# 1_1_3_Interface_board_SWD_FLASH_IO.net
KiCad netlist of a schematic drawn in Altium Designer
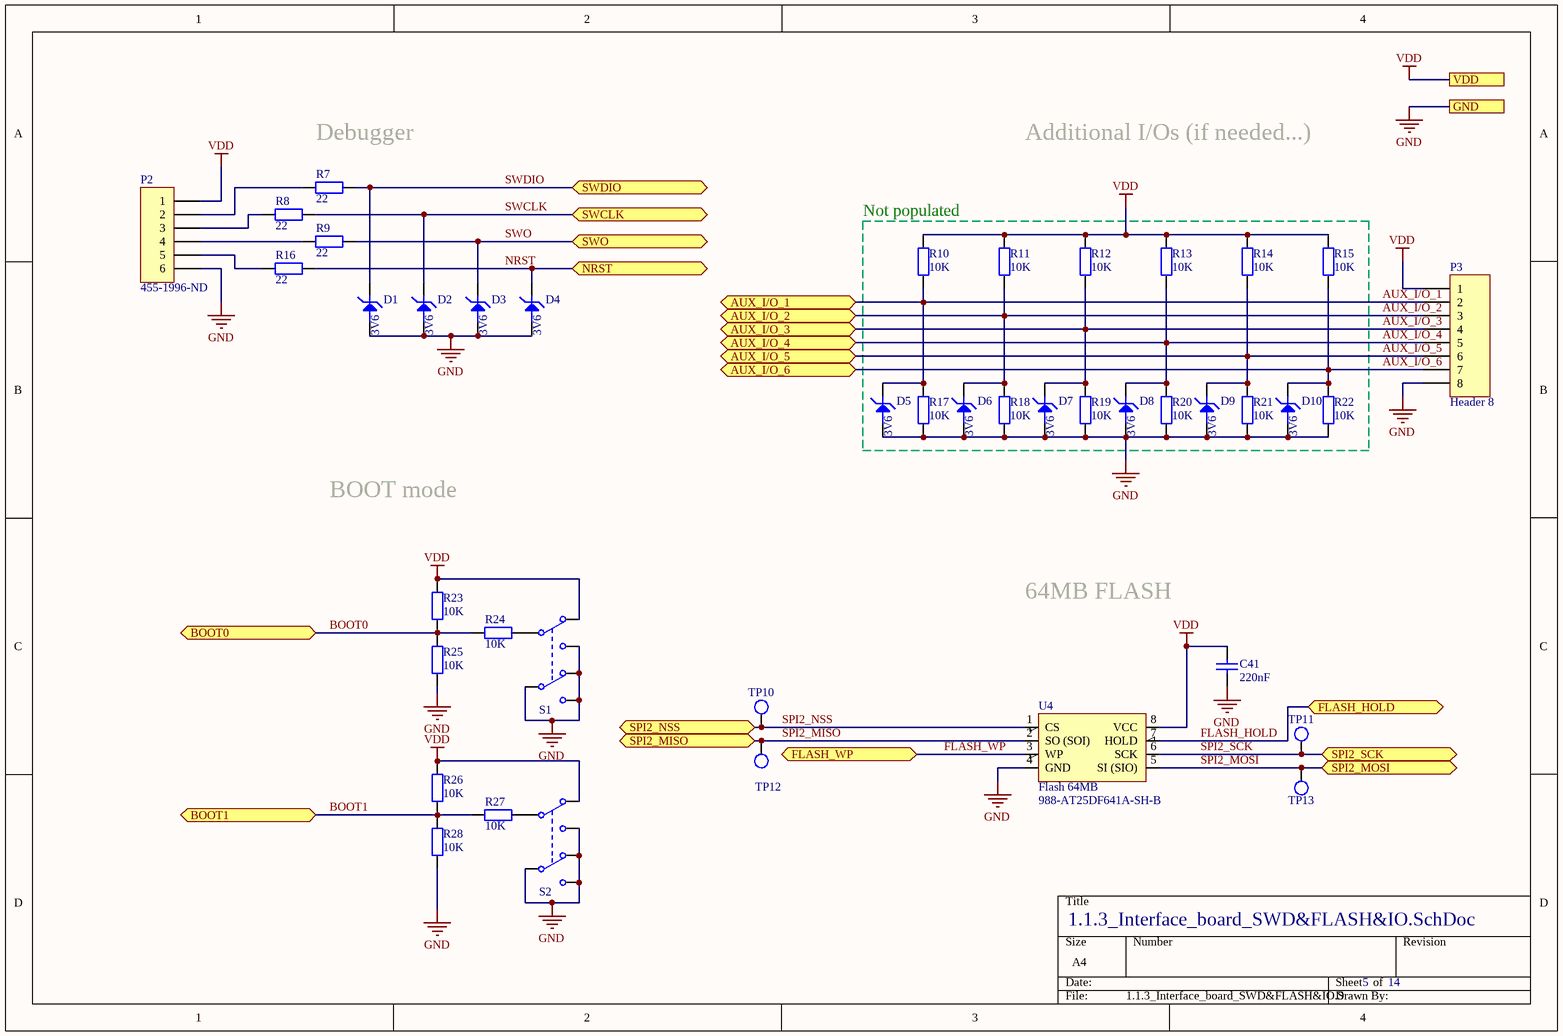
[diagram p0: 1.1.3_Interface_board_SWD&FLASH&IO.SchDoc]

(export (version "E")
  (design (tool "Eeschema 10.0.6"))
  (components
    (comp (ref "C41")
      (value "220nF")
      (footprint "CAP0603R")
      (description "Capacitor")
      (libsource (lib "Rocket_library") (part "C_220nF"))
    )
    (comp (ref "D1")
      (value "3V6")
      (footprint "SOT23")
      (description "Zener Diodes 3.6V 225mW")
      (libsource (lib "Rocket_library") (part "DZ_3V6_MMBZ522"))
    )
    (comp (ref "D2")
      (value "3V6")
      (footprint "SOT23")
      (description "Zener Diodes 3.6V 225mW")
      (libsource (lib "Rocket_library") (part "DZ_3V6_MMBZ522"))
    )
    (comp (ref "D3")
      (value "3V6")
      (footprint "SOT23")
      (description "Zener Diodes 3.6V 225mW")
      (libsource (lib "Rocket_library") (part "DZ_3V6_MMBZ522"))
    )
    (comp (ref "D4")
      (value "3V6")
      (footprint "SOT23")
      (description "Zener Diodes 3.6V 225mW")
      (libsource (lib "Rocket_library") (part "DZ_3V6_MMBZ522"))
    )
    (comp (ref "D5")
      (value "3V6")
      (footprint "SOT23")
      (description "Zener Diodes 3.6V 225mW")
      (libsource (lib "Rocket_library") (part "DZ_3V6_MMBZ522"))
    )
    (comp (ref "D6")
      (value "3V6")
      (footprint "SOT23")
      (description "Zener Diodes 3.6V 225mW")
      (libsource (lib "Rocket_library") (part "DZ_3V6_MMBZ522"))
    )
    (comp (ref "D7")
      (value "3V6")
      (footprint "SOT23")
      (description "Zener Diodes 3.6V 225mW")
      (libsource (lib "Rocket_library") (part "DZ_3V6_MMBZ522"))
    )
    (comp (ref "D8")
      (value "3V6")
      (footprint "SOT23")
      (description "Zener Diodes 3.6V 225mW")
      (libsource (lib "Rocket_library") (part "DZ_3V6_MMBZ522"))
    )
    (comp (ref "D9")
      (value "3V6")
      (footprint "SOT23")
      (description "Zener Diodes 3.6V 225mW")
      (libsource (lib "Rocket_library") (part "DZ_3V6_MMBZ522"))
    )
    (comp (ref "D10")
      (value "3V6")
      (footprint "SOT23")
      (description "Zener Diodes 3.6V 225mW")
      (libsource (lib "Rocket_library") (part "DZ_3V6_MMBZ522"))
    )
    (comp (ref "P2")
      (value "Header 6p JST XA 3A")
      (footprint "CON_JST_XA_ B06B-XASK")
      (fields (field (name "SUPPLIER PART NUMBER 1") "455-1996-ND"))
      (libsource (lib "Rocket_library") (part "Header 6p JST XA 3A"))
    )
    (comp (ref "P3")
      (value "Header 8")
      (footprint "HDR1X8")
      (description "Header, 8-Pin")
      (fields (field (name "PUBLISHER") "Altium Limited"))
      (libsource (lib "Miscellaneous Connectors") (part "Header 8"))
    )
    (comp (ref "R7")
      (value "22")
      (footprint "0603")
      (description "0.25W 22Ohm")
      (libsource (lib "Rocket_library") (part "R_0603_025W_22Ohm"))
    )
    (comp (ref "R8")
      (value "22")
      (footprint "0603")
      (description "0.25W 22Ohm")
      (libsource (lib "Rocket_library") (part "R_0603_025W_22Ohm"))
    )
    (comp (ref "R9")
      (value "22")
      (footprint "0603")
      (description "0.25W 22Ohm")
      (libsource (lib "Rocket_library") (part "R_0603_025W_22Ohm"))
    )
    (comp (ref "R10")
      (value "10K")
      (footprint "0603")
      (description "0.1W 10K")
      (libsource (lib "Rocket_library") (part "R_0603_01W_10K"))
    )
    (comp (ref "R11")
      (value "10K")
      (footprint "0603")
      (description "0.1W 10K")
      (libsource (lib "Rocket_library") (part "R_0603_01W_10K"))
    )
    (comp (ref "R12")
      (value "10K")
      (footprint "0603")
      (description "0.1W 10K")
      (libsource (lib "Rocket_library") (part "R_0603_01W_10K"))
    )
    (comp (ref "R13")
      (value "10K")
      (footprint "0603")
      (description "0.1W 10K")
      (libsource (lib "Rocket_library") (part "R_0603_01W_10K"))
    )
    (comp (ref "R14")
      (value "10K")
      (footprint "0603")
      (description "0.1W 10K")
      (libsource (lib "Rocket_library") (part "R_0603_01W_10K"))
    )
    (comp (ref "R15")
      (value "10K")
      (footprint "0603")
      (description "0.1W 10K")
      (libsource (lib "Rocket_library") (part "R_0603_01W_10K"))
    )
    (comp (ref "R16")
      (value "22")
      (footprint "0603")
      (description "0.25W 22Ohm")
      (libsource (lib "Rocket_library") (part "R_0603_025W_22Ohm"))
    )
    (comp (ref "R17")
      (value "10K")
      (footprint "0603")
      (description "0.1W 10K")
      (libsource (lib "Rocket_library") (part "R_0603_01W_10K"))
    )
    (comp (ref "R18")
      (value "10K")
      (footprint "0603")
      (description "0.1W 10K")
      (libsource (lib "Rocket_library") (part "R_0603_01W_10K"))
    )
    (comp (ref "R19")
      (value "10K")
      (footprint "0603")
      (description "0.1W 10K")
      (libsource (lib "Rocket_library") (part "R_0603_01W_10K"))
    )
    (comp (ref "R20")
      (value "10K")
      (footprint "0603")
      (description "0.1W 10K")
      (libsource (lib "Rocket_library") (part "R_0603_01W_10K"))
    )
    (comp (ref "R21")
      (value "10K")
      (footprint "0603")
      (description "0.1W 10K")
      (libsource (lib "Rocket_library") (part "R_0603_01W_10K"))
    )
    (comp (ref "R22")
      (value "10K")
      (footprint "0603")
      (description "0.1W 10K")
      (libsource (lib "Rocket_library") (part "R_0603_01W_10K"))
    )
    (comp (ref "R23")
      (value "10K")
      (footprint "0603")
      (description "0.1W 10K")
      (libsource (lib "Rocket_library") (part "R_0603_01W_10K"))
    )
    (comp (ref "R24")
      (value "10K")
      (footprint "0603")
      (description "0.1W 10K")
      (libsource (lib "") (part "R_0603_01W_10K_1"))
    )
    (comp (ref "R25")
      (value "10K")
      (footprint "0603")
      (description "0.1W 10K")
      (libsource (lib "Rocket_library") (part "R_0603_01W_10K"))
    )
    (comp (ref "R26")
      (value "10K")
      (footprint "0603")
      (description "0.1W 10K")
      (libsource (lib "Rocket_library") (part "R_0603_01W_10K"))
    )
    (comp (ref "R27")
      (value "10K")
      (footprint "0603")
      (description "0.1W 10K")
      (libsource (lib "") (part "R_0603_01W_10K_1"))
    )
    (comp (ref "R28")
      (value "10K")
      (footprint "0603")
      (description "0.1W 10K")
      (libsource (lib "Rocket_library") (part "R_0603_01W_10K"))
    )
    (comp (ref "S1")
      (value "SW DPDT")
      (footprint "SMD Slide Switches ON-ON")
      (description "Switch")
      (libsource (lib "Rocket_library") (part "SW DPDT"))
    )
    (comp (ref "S2")
      (value "SW DPDT")
      (footprint "SMD Slide Switches ON-ON")
      (description "Switch")
      (libsource (lib "Rocket_library") (part "SW DPDT"))
    )
    (comp (ref "TP10")
      (value "Test point")
      (footprint "TP")
      (libsource (lib "Rocket_library") (part "Test point"))
    )
    (comp (ref "TP11")
      (value "Test point")
      (footprint "TP")
      (libsource (lib "Rocket_library") (part "Test point"))
    )
    (comp (ref "TP12")
      (value "Test point")
      (footprint "TP")
      (libsource (lib "Rocket_library") (part "Test point"))
    )
    (comp (ref "TP13")
      (value "Test point")
      (footprint "TP")
      (libsource (lib "Rocket_library") (part "Test point"))
    )
    (comp (ref "U4")
      (value "Flash 64MB")
      (footprint "SOIC-8")
      (fields (field (name "SUPPLIER PART NUMBER 1") "988-AT25DF641A-SH-B"))
      (libsource (lib "Rocket_library") (part "Flash 64MB SPI"))
    )
  )
  (nets
    (net (code "1") (name "/AUX_I{slash}O_1") (class "Default")
      (node (ref "D5") (pin "3") (pintype "passive"))
      (node (ref "P3") (pin "2") (pinfunction "2_2") (pintype "passive"))
      (node (ref "R10") (pin "1") (pinfunction "1_1") (pintype "passive"))
      (node (ref "R17") (pin "2") (pinfunction "2_2") (pintype "passive"))
    )
    (net (code "2") (name "/AUX_I{slash}O_2") (class "Default")
      (node (ref "D6") (pin "3") (pintype "passive"))
      (node (ref "P3") (pin "3") (pinfunction "3_3") (pintype "passive"))
      (node (ref "R11") (pin "1") (pinfunction "1_1") (pintype "passive"))
      (node (ref "R18") (pin "2") (pinfunction "2_2") (pintype "passive"))
    )
    (net (code "3") (name "/AUX_I{slash}O_3") (class "Default")
      (node (ref "D7") (pin "3") (pintype "passive"))
      (node (ref "P3") (pin "4") (pinfunction "4_4") (pintype "passive"))
      (node (ref "R12") (pin "1") (pinfunction "1_1") (pintype "passive"))
      (node (ref "R19") (pin "2") (pinfunction "2_2") (pintype "passive"))
    )
    (net (code "4") (name "/AUX_I{slash}O_4") (class "Default")
      (node (ref "D8") (pin "3") (pintype "passive"))
      (node (ref "P3") (pin "5") (pinfunction "5_5") (pintype "passive"))
      (node (ref "R13") (pin "1") (pinfunction "1_1") (pintype "passive"))
      (node (ref "R20") (pin "2") (pinfunction "2_2") (pintype "passive"))
    )
    (net (code "5") (name "/AUX_I{slash}O_5") (class "Default")
      (node (ref "D9") (pin "3") (pintype "passive"))
      (node (ref "P3") (pin "6") (pinfunction "6_6") (pintype "passive"))
      (node (ref "R14") (pin "1") (pinfunction "1_1") (pintype "passive"))
      (node (ref "R21") (pin "2") (pinfunction "2_2") (pintype "passive"))
    )
    (net (code "6") (name "/AUX_I{slash}O_6") (class "Default")
      (node (ref "D10") (pin "3") (pintype "passive"))
      (node (ref "P3") (pin "7") (pinfunction "7_7") (pintype "passive"))
      (node (ref "R15") (pin "1") (pinfunction "1_1") (pintype "passive"))
      (node (ref "R22") (pin "2") (pinfunction "2_2") (pintype "passive"))
    )
    (net (code "7") (name "/BOOT0") (class "Default")
      (node (ref "R23") (pin "1") (pinfunction "1_1") (pintype "passive"))
      (node (ref "R24") (pin "2") (pinfunction "2_2") (pintype "passive"))
      (node (ref "R25") (pin "2") (pinfunction "2_2") (pintype "passive"))
    )
    (net (code "8") (name "/BOOT1") (class "Default")
      (node (ref "R26") (pin "1") (pinfunction "1_1") (pintype "passive"))
      (node (ref "R27") (pin "2") (pinfunction "2_2") (pintype "passive"))
      (node (ref "R28") (pin "2") (pinfunction "2_2") (pintype "passive"))
    )
    (net (code "9") (name "/FLASH_HOLD") (class "Default")
      (node (ref "U4") (pin "7") (pinfunction "HOLD_7") (pintype "passive"))
    )
    (net (code "10") (name "/FLASH_WP") (class "Default")
      (node (ref "U4") (pin "3") (pinfunction "WP_3") (pintype "passive"))
    )
    (net (code "11") (name "/NRST") (class "Default")
      (node (ref "D4") (pin "3") (pintype "passive"))
      (node (ref "R16") (pin "2") (pinfunction "2_2") (pintype "passive"))
    )
    (net (code "12") (name "/SPI2_MISO") (class "Default")
      (node (ref "TP12") (pin "1") (pinfunction "1_1") (pintype "passive"))
      (node (ref "U4") (pin "2") (pinfunction "SO_(SOI)_2") (pintype "passive"))
    )
    (net (code "13") (name "/SPI2_MOSI") (class "Default")
      (node (ref "TP13") (pin "1") (pinfunction "1_1") (pintype "passive"))
      (node (ref "U4") (pin "5") (pinfunction "SI_(SIO)_5") (pintype "passive"))
    )
    (net (code "14") (name "/SPI2_NSS") (class "Default")
      (node (ref "TP10") (pin "1") (pinfunction "1_1") (pintype "passive"))
      (node (ref "U4") (pin "1") (pinfunction "CS_1") (pintype "passive"))
    )
    (net (code "15") (name "/SPI2_SCK") (class "Default")
      (node (ref "TP11") (pin "1") (pinfunction "1_1") (pintype "passive"))
      (node (ref "U4") (pin "6") (pinfunction "SCK_6") (pintype "passive"))
    )
    (net (code "16") (name "/SWCLK") (class "Default")
      (node (ref "D2") (pin "3") (pintype "passive"))
      (node (ref "R8") (pin "2") (pinfunction "2_2") (pintype "passive"))
    )
    (net (code "17") (name "/SWDIO") (class "Default")
      (node (ref "D1") (pin "3") (pintype "passive"))
      (node (ref "R7") (pin "2") (pinfunction "2_2") (pintype "passive"))
    )
    (net (code "18") (name "/SWO") (class "Default")
      (node (ref "D3") (pin "3") (pintype "passive"))
      (node (ref "R9") (pin "2") (pinfunction "2_2") (pintype "passive"))
    )
    (net (code "19") (name "GND") (class "Default")
      (node (ref "C41") (pin "1") (pinfunction "1_1") (pintype "passive"))
      (node (ref "D1") (pin "1") (pintype "passive"))
      (node (ref "D10") (pin "1") (pintype "passive"))
      (node (ref "D2") (pin "1") (pintype "passive"))
      (node (ref "D3") (pin "1") (pintype "passive"))
      (node (ref "D4") (pin "1") (pintype "passive"))
      (node (ref "D5") (pin "1") (pintype "passive"))
      (node (ref "D6") (pin "1") (pintype "passive"))
      (node (ref "D7") (pin "1") (pintype "passive"))
      (node (ref "D8") (pin "1") (pintype "passive"))
      (node (ref "D9") (pin "1") (pintype "passive"))
      (node (ref "P2") (pin "6") (pinfunction "6_6") (pintype "passive"))
      (node (ref "P3") (pin "8") (pinfunction "8_8") (pintype "passive"))
      (node (ref "R17") (pin "1") (pinfunction "1_1") (pintype "passive"))
      (node (ref "R18") (pin "1") (pinfunction "1_1") (pintype "passive"))
      (node (ref "R19") (pin "1") (pinfunction "1_1") (pintype "passive"))
      (node (ref "R20") (pin "1") (pinfunction "1_1") (pintype "passive"))
      (node (ref "R21") (pin "1") (pinfunction "1_1") (pintype "passive"))
      (node (ref "R22") (pin "1") (pinfunction "1_1") (pintype "passive"))
      (node (ref "R25") (pin "1") (pinfunction "1_1") (pintype "passive"))
      (node (ref "R28") (pin "1") (pinfunction "1_1") (pintype "passive"))
      (node (ref "S1") (pin "1") (pinfunction "NO1_1") (pintype "passive"))
      (node (ref "S1") (pin "4") (pinfunction "NO2_4") (pintype "passive"))
      (node (ref "S1") (pin "5") (pinfunction "COMMON2_5") (pintype "passive"))
      (node (ref "S1") (pin "6") (pinfunction "NC2_6") (pintype "passive"))
      (node (ref "S2") (pin "1") (pinfunction "NO1_1") (pintype "passive"))
      (node (ref "S2") (pin "4") (pinfunction "NO2_4") (pintype "passive"))
      (node (ref "S2") (pin "5") (pinfunction "COMMON2_5") (pintype "passive"))
      (node (ref "S2") (pin "6") (pinfunction "NC2_6") (pintype "passive"))
      (node (ref "U4") (pin "4") (pinfunction "GND_4") (pintype "passive"))
    )
    (net (code "20") (name "Net-(P2-Pad2)") (class "Default")
      (node (ref "P2") (pin "2") (pinfunction "2_2") (pintype "passive"))
      (node (ref "R7") (pin "1") (pinfunction "1_1") (pintype "passive"))
    )
    (net (code "21") (name "Net-(P2-Pad3)") (class "Default")
      (node (ref "P2") (pin "3") (pinfunction "3_3") (pintype "passive"))
      (node (ref "R8") (pin "1") (pinfunction "1_1") (pintype "passive"))
    )
    (net (code "22") (name "Net-(P2-Pad4)") (class "Default")
      (node (ref "P2") (pin "4") (pinfunction "4_4") (pintype "passive"))
      (node (ref "R9") (pin "1") (pinfunction "1_1") (pintype "passive"))
    )
    (net (code "23") (name "Net-(P2-Pad5)") (class "Default")
      (node (ref "P2") (pin "5") (pinfunction "5_5") (pintype "passive"))
      (node (ref "R16") (pin "1") (pinfunction "1_1") (pintype "passive"))
    )
    (net (code "24") (name "Net-(S1-COMMON1)") (class "Default")
      (node (ref "R24") (pin "1") (pinfunction "1_1") (pintype "passive"))
      (node (ref "S1") (pin "2") (pinfunction "COMMON1_2") (pintype "passive"))
    )
    (net (code "25") (name "Net-(S2-COMMON1)") (class "Default")
      (node (ref "R27") (pin "1") (pinfunction "1_1") (pintype "passive"))
      (node (ref "S2") (pin "2") (pinfunction "COMMON1_2") (pintype "passive"))
    )
    (net (code "26") (name "VDD") (class "Default")
      (node (ref "C41") (pin "2") (pinfunction "2_2") (pintype "passive"))
      (node (ref "P2") (pin "1") (pinfunction "1_1") (pintype "passive"))
      (node (ref "P3") (pin "1") (pinfunction "1_1") (pintype "passive"))
      (node (ref "R10") (pin "2") (pinfunction "2_2") (pintype "passive"))
      (node (ref "R11") (pin "2") (pinfunction "2_2") (pintype "passive"))
      (node (ref "R12") (pin "2") (pinfunction "2_2") (pintype "passive"))
      (node (ref "R13") (pin "2") (pinfunction "2_2") (pintype "passive"))
      (node (ref "R14") (pin "2") (pinfunction "2_2") (pintype "passive"))
      (node (ref "R15") (pin "2") (pinfunction "2_2") (pintype "passive"))
      (node (ref "R23") (pin "2") (pinfunction "2_2") (pintype "passive"))
      (node (ref "R26") (pin "2") (pinfunction "2_2") (pintype "passive"))
      (node (ref "S1") (pin "3") (pinfunction "NC1_3") (pintype "passive"))
      (node (ref "S2") (pin "3") (pinfunction "NC1_3") (pintype "passive"))
      (node (ref "U4") (pin "8") (pinfunction "VCC_8") (pintype "passive"))
    )
  )
)
